# Decade_Counter.net
KiCad netlist of a schematic drawn in EAGLE
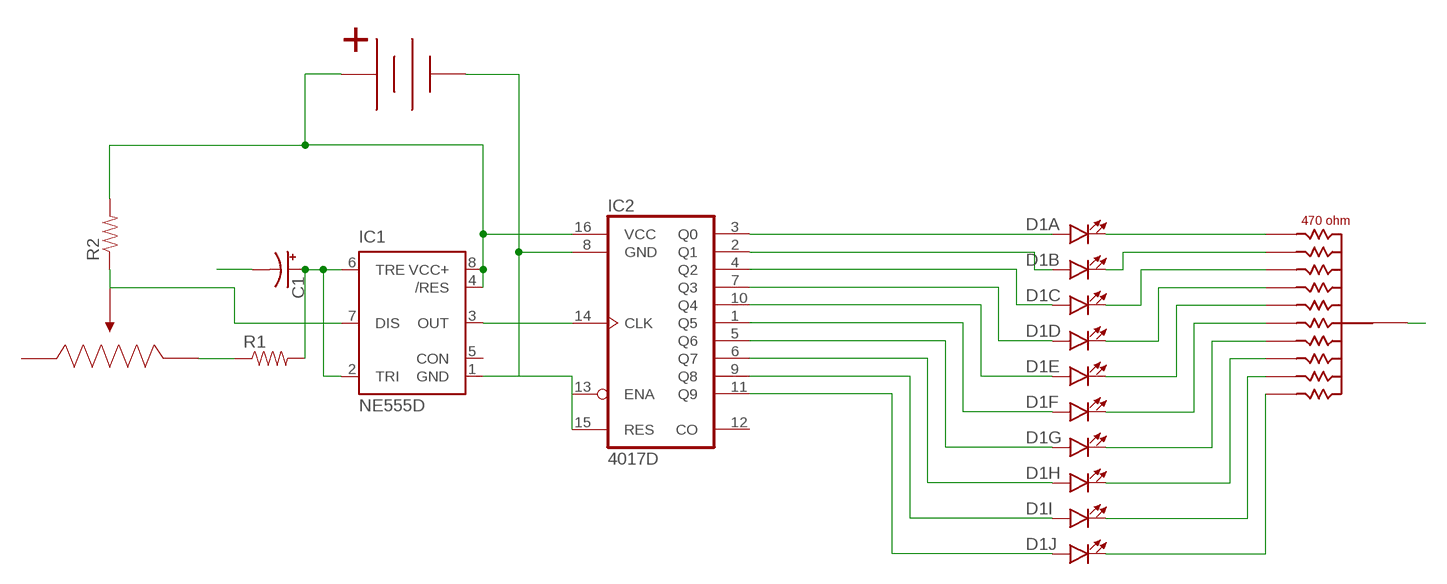
[diagram p0: schematic, sheet 1]

(export (version "E")
  (design (tool "Eeschema 10.0.6"))
  (components
    (comp (ref "470OHM")
      (value "470 ohm")
      (footprint "eagle-import:11-PIN-RESISTOR")
      (libsource (lib "eagle-import") (part "11PI_RESISTOR_COMMON"))
    )
    (comp (ref "C1")
      (value "CAP_POLPTH1")
      (footprint "eagle-import:CPOL-RADIAL-100UF-25V")
      (libsource (lib "eagle-import") (part "CAP_POLPTH1"))
    )
    (comp (ref "D1")
      (value "LED_BARGRAPH_10")
      (footprint "eagle-import:LED_BARGAPH_10")
      (libsource (lib "eagle-import") (part "LED_BARGRAPH_10"))
    )
    (comp (ref "IC1")
      (value "NE555D")
      (footprint "eagle-import:SO08")
      (libsource (lib "eagle-import") (part "NE555D"))
    )
    (comp (ref "IC2")
      (value "4017D")
      (footprint "eagle-import:SO16")
      (libsource (lib "eagle-import") (part "4017D"))
    )
    (comp (ref "R1")
      (value "RESISTOR0805-RES")
      (footprint "eagle-import:0805")
      (libsource (lib "eagle-import") (part "RESISTOR0805-RES"))
    )
    (comp (ref "R2")
      (value "RESISTOR0805-RES")
      (footprint "eagle-import:0805")
      (libsource (lib "eagle-import") (part "RESISTOR0805-RES"))
    )
    (comp (ref "U$1")
      (value "VERTICAL_TRIM_POT")
      (footprint "eagle-import:TRIM-POT-VERTICLE")
      (libsource (lib "eagle-import") (part "VERTICAL_TRIM_POT"))
    )
    (comp (ref "U$2")
      (value "COIN-BATTERY-12MM-BOTTOM")
      (footprint "eagle-import:BATTCON_12MM_BOTTOM")
      (libsource (lib "eagle-import") (part "COIN-BATTERY-12MM-BOTTOM"))
    )
  )
  (nets
    (net (code "1") (name "/GND") (class "Default")
      (node (ref "470OHM") (pin "COMMON") (pinfunction "COMMON_COMMON") (pintype "bidirectional"))
      (node (ref "C1") (pin "2") (pinfunction "-_2") (pintype "passive"))
      (node (ref "IC1") (pin "1") (pinfunction "GND_1") (pintype "power_in"))
      (node (ref "IC2") (pin "13") (pinfunction "ENA_13") (pintype "input"))
      (node (ref "IC2") (pin "15") (pinfunction "RES_15") (pintype "input"))
      (node (ref "IC2") (pin "8") (pinfunction "GND_8") (pintype "bidirectional"))
      (node (ref "U$2") (pin "GND") (pinfunction "GND_GND") (pintype "bidirectional"))
    )
    (net (code "2") (name "Net-(C1-+)") (class "Default")
      (node (ref "C1") (pin "1") (pinfunction "+_1") (pintype "passive"))
      (node (ref "IC1") (pin "2") (pinfunction "TRI_2") (pintype "input"))
      (node (ref "IC1") (pin "6") (pinfunction "TRE_6") (pintype "input"))
      (node (ref "R1") (pin "2") (pinfunction "2_2") (pintype "passive"))
    )
    (net (code "3") (name "Net-(D1A-A)") (class "Default")
      (node (ref "D1") (pin "1") (pinfunction "A_1") (pintype "passive"))
      (node (ref "IC2") (pin "3") (pinfunction "Q0_3") (pintype "output"))
    )
    (net (code "4") (name "Net-(D1A-C)") (class "Default")
      (node (ref "470OHM") (pin "1") (pinfunction "1_1") (pintype "bidirectional"))
      (node (ref "D1") (pin "20") (pinfunction "C_20") (pintype "passive"))
    )
    (net (code "5") (name "Net-(D1B-A)") (class "Default")
      (node (ref "D1") (pin "2") (pinfunction "A_2") (pintype "passive"))
      (node (ref "IC2") (pin "2") (pinfunction "Q1_2") (pintype "output"))
    )
    (net (code "6") (name "Net-(D1B-C)") (class "Default")
      (node (ref "470OHM") (pin "2") (pinfunction "2_2") (pintype "bidirectional"))
      (node (ref "D1") (pin "19") (pinfunction "C_19") (pintype "passive"))
    )
    (net (code "7") (name "Net-(D1C-A)") (class "Default")
      (node (ref "D1") (pin "3") (pinfunction "A_3") (pintype "passive"))
      (node (ref "IC2") (pin "4") (pinfunction "Q2_4") (pintype "output"))
    )
    (net (code "8") (name "Net-(D1C-C)") (class "Default")
      (node (ref "470OHM") (pin "3") (pinfunction "3_3") (pintype "bidirectional"))
      (node (ref "D1") (pin "18") (pinfunction "C_18") (pintype "passive"))
    )
    (net (code "9") (name "Net-(D1D-A)") (class "Default")
      (node (ref "D1") (pin "4") (pinfunction "A_4") (pintype "passive"))
      (node (ref "IC2") (pin "7") (pinfunction "Q3_7") (pintype "output"))
    )
    (net (code "10") (name "Net-(D1D-C)") (class "Default")
      (node (ref "470OHM") (pin "4") (pinfunction "4_4") (pintype "bidirectional"))
      (node (ref "D1") (pin "17") (pinfunction "C_17") (pintype "passive"))
    )
    (net (code "11") (name "Net-(D1E-A)") (class "Default")
      (node (ref "D1") (pin "5") (pinfunction "A_5") (pintype "passive"))
      (node (ref "IC2") (pin "10") (pinfunction "Q4_10") (pintype "output"))
    )
    (net (code "12") (name "Net-(D1E-C)") (class "Default")
      (node (ref "470OHM") (pin "5") (pinfunction "5_5") (pintype "bidirectional"))
      (node (ref "D1") (pin "16") (pinfunction "C_16") (pintype "passive"))
    )
    (net (code "13") (name "Net-(D1F-A)") (class "Default")
      (node (ref "D1") (pin "6") (pinfunction "A_6") (pintype "passive"))
      (node (ref "IC2") (pin "1") (pinfunction "Q5_1") (pintype "output"))
    )
    (net (code "14") (name "Net-(D1F-C)") (class "Default")
      (node (ref "470OHM") (pin "6") (pinfunction "6_6") (pintype "bidirectional"))
      (node (ref "D1") (pin "15") (pinfunction "C_15") (pintype "passive"))
    )
    (net (code "15") (name "Net-(D1G-A)") (class "Default")
      (node (ref "D1") (pin "7") (pinfunction "A_7") (pintype "passive"))
      (node (ref "IC2") (pin "5") (pinfunction "Q6_5") (pintype "output"))
    )
    (net (code "16") (name "Net-(D1G-C)") (class "Default")
      (node (ref "470OHM") (pin "7") (pinfunction "7_7") (pintype "bidirectional"))
      (node (ref "D1") (pin "14") (pinfunction "C_14") (pintype "passive"))
    )
    (net (code "17") (name "Net-(D1H-A)") (class "Default")
      (node (ref "D1") (pin "8") (pinfunction "A_8") (pintype "passive"))
      (node (ref "IC2") (pin "6") (pinfunction "Q7_6") (pintype "output"))
    )
    (net (code "18") (name "Net-(D1H-C)") (class "Default")
      (node (ref "470OHM") (pin "8") (pinfunction "8_8") (pintype "bidirectional"))
      (node (ref "D1") (pin "13") (pinfunction "C_13") (pintype "passive"))
    )
    (net (code "19") (name "Net-(D1I-A)") (class "Default")
      (node (ref "D1") (pin "9") (pinfunction "A_9") (pintype "passive"))
      (node (ref "IC2") (pin "9") (pinfunction "Q8_9") (pintype "output"))
    )
    (net (code "20") (name "Net-(D1I-C)") (class "Default")
      (node (ref "470OHM") (pin "9") (pinfunction "9_9") (pintype "bidirectional"))
      (node (ref "D1") (pin "12") (pinfunction "C_12") (pintype "passive"))
    )
    (net (code "21") (name "Net-(D1J-A)") (class "Default")
      (node (ref "D1") (pin "10") (pinfunction "A_10") (pintype "passive"))
      (node (ref "IC2") (pin "11") (pinfunction "Q9_11") (pintype "output"))
    )
    (net (code "22") (name "Net-(D1J-C)") (class "Default")
      (node (ref "470OHM") (pin "10") (pinfunction "10_10") (pintype "bidirectional"))
      (node (ref "D1") (pin "11") (pinfunction "C_11") (pintype "passive"))
    )
    (net (code "23") (name "Net-(IC1-DIS)") (class "Default")
      (node (ref "IC1") (pin "7") (pinfunction "DIS_7") (pintype "input"))
      (node (ref "R2") (pin "1") (pinfunction "1_1") (pintype "passive"))
      (node (ref "U$1") (pin "WIPER2") (pinfunction "WIPER_WIPER2") (pintype "bidirectional"))
    )
    (net (code "24") (name "Net-(IC1-OUT)") (class "Default")
      (node (ref "IC1") (pin "3") (pinfunction "OUT_3") (pintype "output"))
      (node (ref "IC2") (pin "14") (pinfunction "CLK_14") (pintype "input"))
    )
    (net (code "25") (name "Net-(IC1-VCC+)") (class "Default")
      (node (ref "IC1") (pin "4") (pinfunction "/RES_4") (pintype "input"))
      (node (ref "IC1") (pin "8") (pinfunction "VCC+_8") (pintype "power_in"))
      (node (ref "IC2") (pin "16") (pinfunction "VCC_16") (pintype "bidirectional"))
      (node (ref "R2") (pin "2") (pinfunction "2_2") (pintype "passive"))
      (node (ref "U$2") (pin "PWR@1") (pinfunction "PWR_PWR@1") (pintype "bidirectional"))
      (node (ref "U$2") (pin "PWR@2") (pinfunction "PWR_PWR@2") (pintype "bidirectional"))
    )
    (net (code "26") (name "Net-(R1-Pad1)") (class "Default")
      (node (ref "R1") (pin "1") (pinfunction "1_1") (pintype "passive"))
      (node (ref "U$1") (pin "3") (pinfunction "3_3") (pintype "bidirectional"))
    )
    (net (code "27") (name "unconnected-(IC1-CON-Pad5)") (class "Default")
      (node (ref "IC1") (pin "5") (pinfunction "CON_5") (pintype "input"))
    )
    (net (code "28") (name "unconnected-(IC2-CO-Pad12)") (class "Default")
      (node (ref "IC2") (pin "12") (pinfunction "CO_12") (pintype "output"))
    )
    (net (code "29") (name "unconnected-(U$1-Pad1)") (class "Default")
      (node (ref "U$1") (pin "1") (pinfunction "1_1") (pintype "bidirectional"))
    )
  )
)
